# Top.net
KiCad netlist of a schematic drawn in Altium Designer
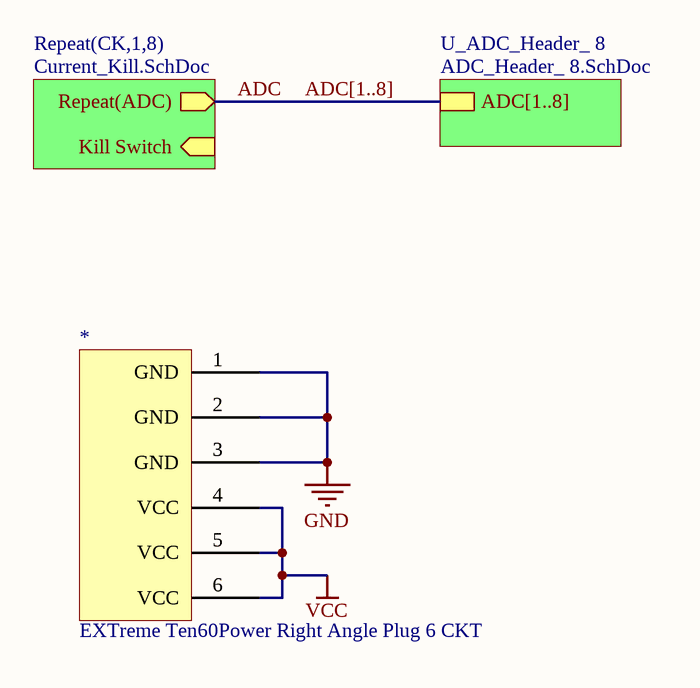
[diagram p0: Top.SchDoc]

(export (version "E")
  (design (tool "Eeschema 10.0.6"))
  (components
    (comp (ref "*")
      (value "EXTreme Ten60Power Right Angle Plug 6 CKT")
      (footprint "EXTreme Ten60Power Right Angle Plug 6 CKT")
      (libsource (lib "Molex_DT") (part "EXTreme Ten60Power Right Angle Plug 6 CKT"))
    )
  )
  (nets
    (net (code "3") (name "GND") (class "Default")
      (node (ref "*") (pin "1") (pinfunction "GND_1") (pintype "passive"))
      (node (ref "*") (pin "2") (pinfunction "GND_2") (pintype "passive"))
      (node (ref "*") (pin "3") (pinfunction "GND_3") (pintype "passive"))
    )
    (net (code "4") (name "VCC") (class "Default")
      (node (ref "*") (pin "4") (pinfunction "VCC_4") (pintype "passive"))
      (node (ref "*") (pin "5") (pinfunction "VCC_5") (pintype "passive"))
      (node (ref "*") (pin "6") (pinfunction "VCC_6") (pintype "passive"))
    )
  )
)
